# SCH_Bitcoin-Tracker_2024-07-20.net
KiCad netlist of a schematic drawn in EasyEDA
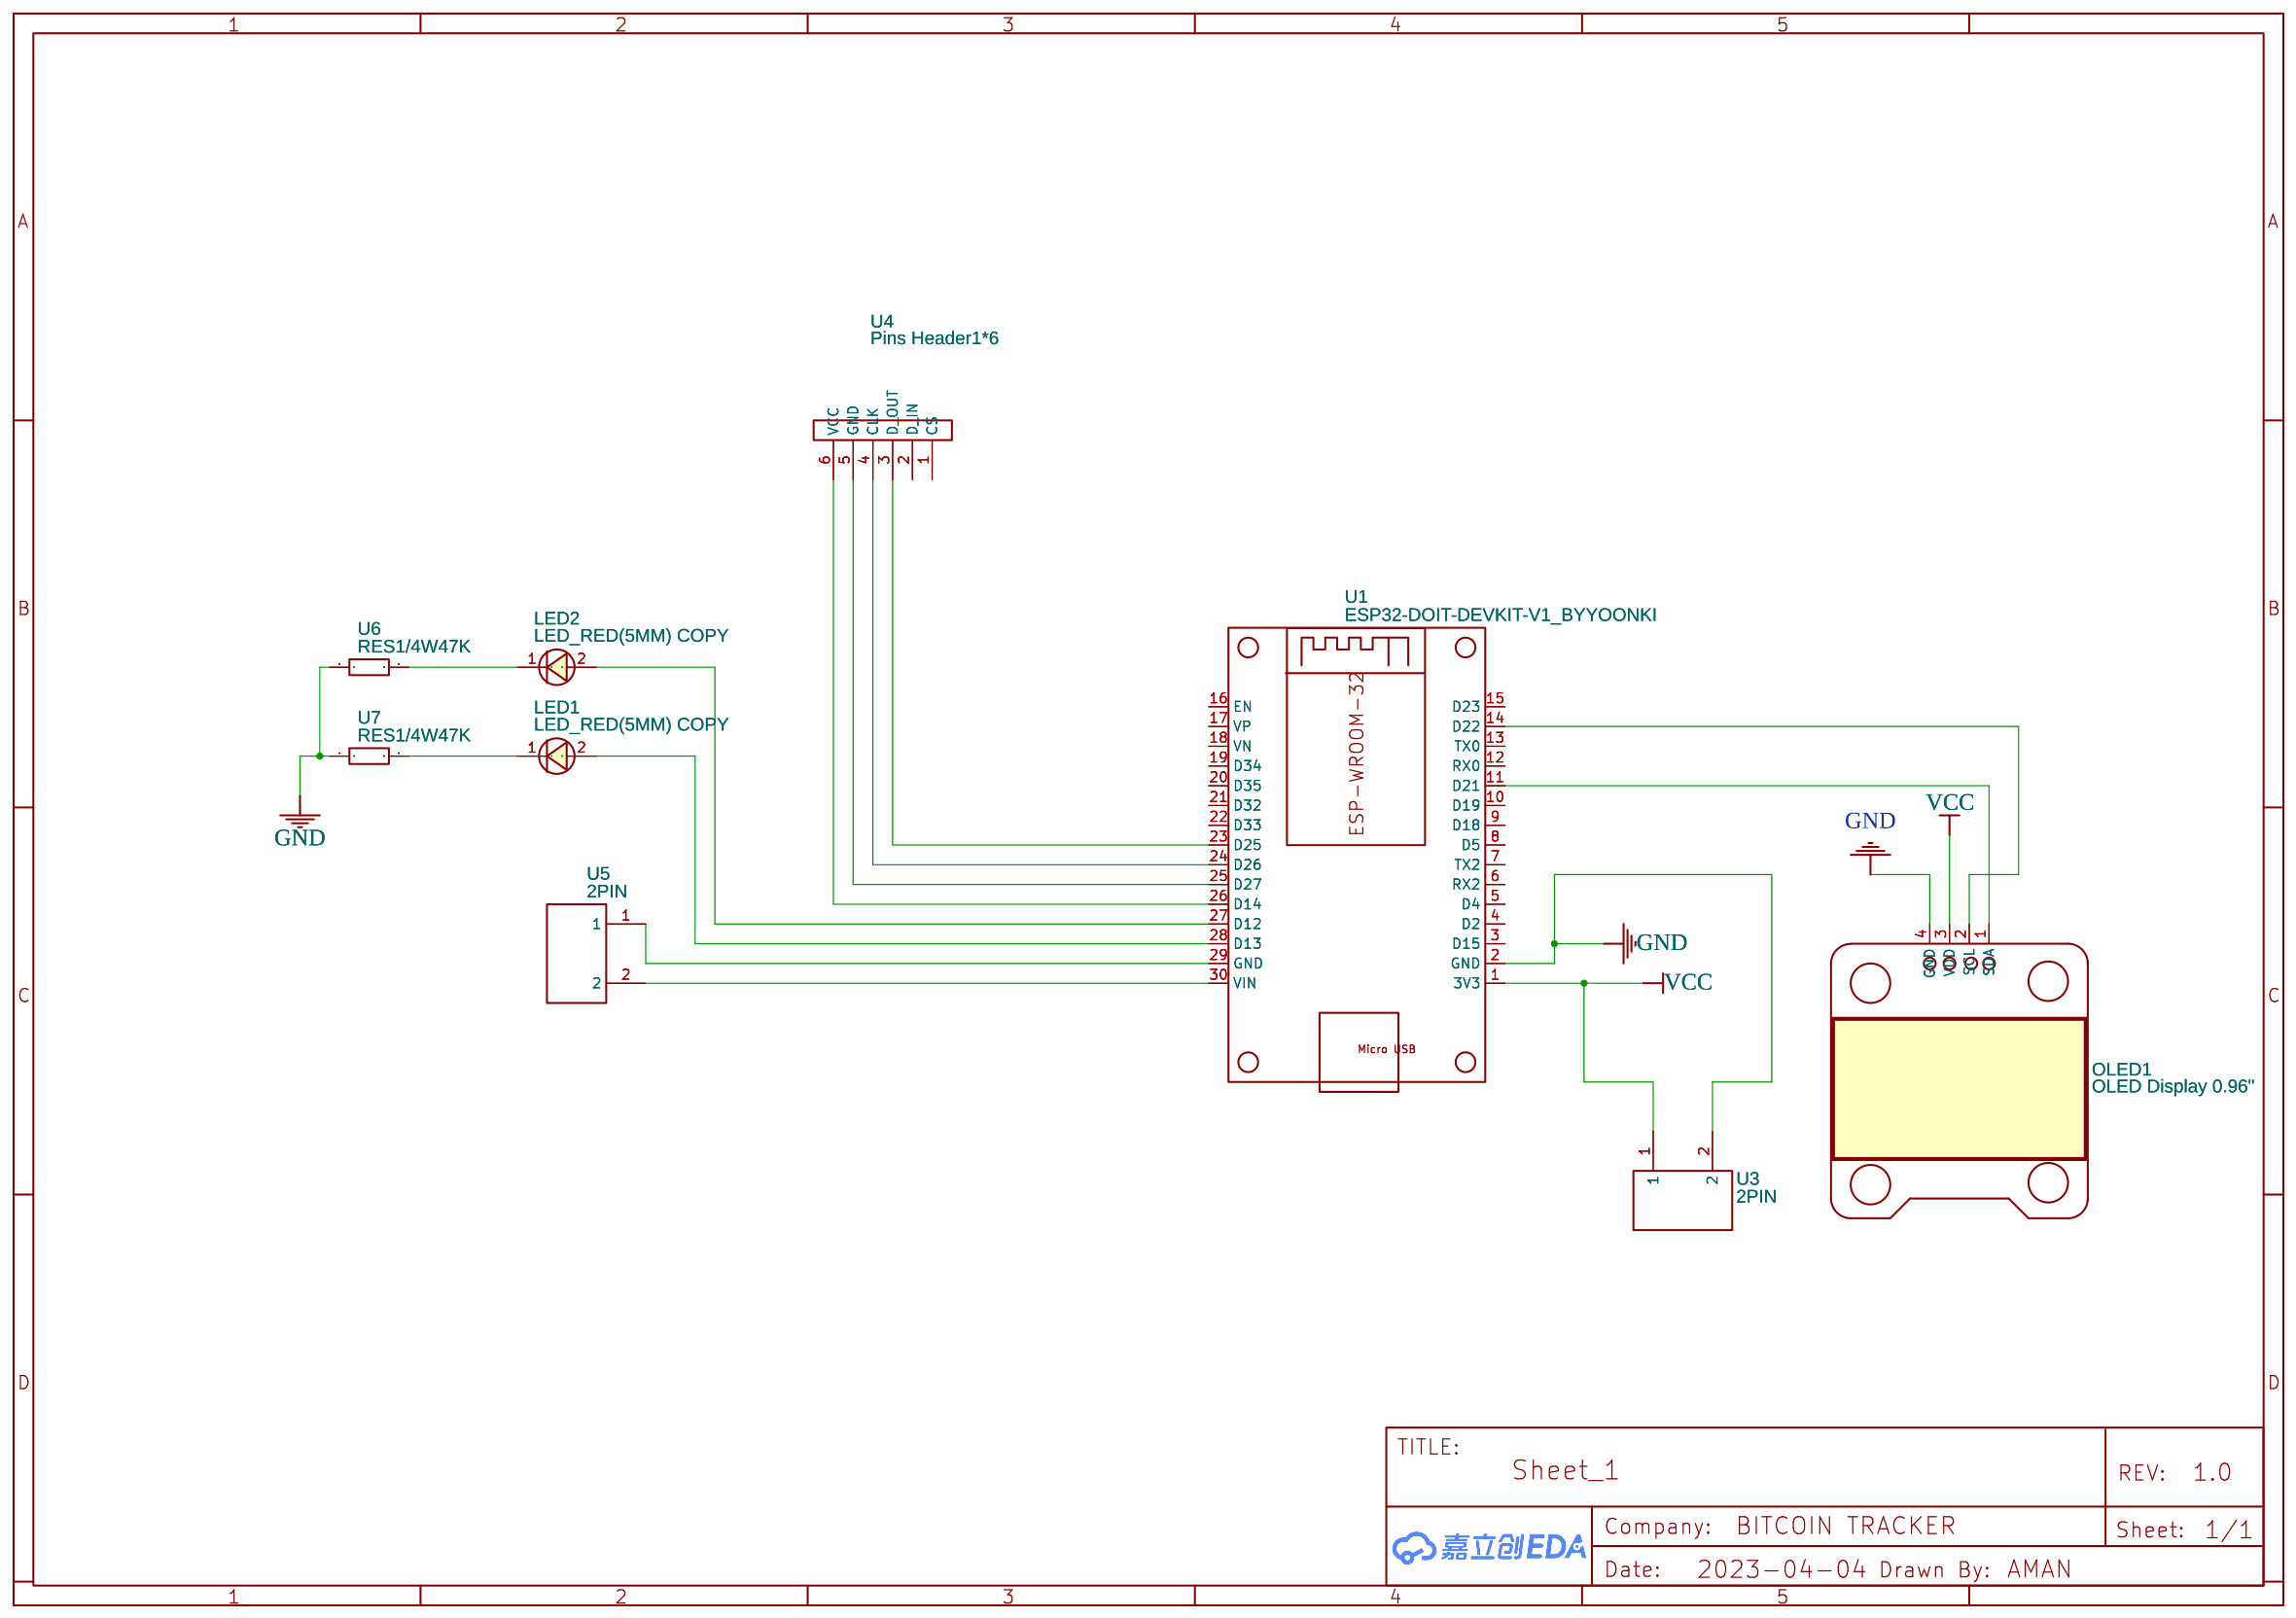
[diagram p0: schematic sheet]

(export (version "E")
  (design (tool "Eeschema 10.0.6"))
  (components
    (comp (ref "LED1")
      (value "LED_RED(5MM) COPY")
      (fields (field (name "Manufacturer Part") "LED 5MM"))
      (libsource (lib "") (part "LED_RED(5MM) COPY"))
    )
    (comp (ref "LED2")
      (value "LED_RED(5MM) COPY")
      (fields (field (name "Manufacturer Part") "LED 5MM"))
      (libsource (lib "") (part "LED_RED(5MM) COPY"))
    )
    (comp (ref "OLED1")
      (value "OLED Display 0.96\"")
      (libsource (lib "") (part "OLED Display 0.96{dblquote}"))
    )
    (comp (ref "U1")
      (value "ESP32-DOIT-DEVKIT-V1_BYYOONKI")
      (fields (field (name "Manufacturer Part") "ESP32_DOIT_DEVKIT_30_PIN"))
      (libsource (lib "") (part "ESP32-DOIT-DEVKIT-V1_BYYOONKI"))
    )
    (comp (ref "U3") (value "2PIN") (libsource (lib "") (part "2PIN_1")))
    (comp (ref "U4") (value "Pins Header1*6") (libsource (lib "") (part "Pins Header1*6")))
    (comp (ref "U5") (value "2PIN") (libsource (lib "") (part "2PIN")))
    (comp (ref "U6") (value "RES1/4W47K") (libsource (lib "") (part "RES1/4W47K")))
    (comp (ref "U7") (value "RES1/4W47K") (libsource (lib "") (part "RES1/4W47K")))
  )
  (nets
    (net (code "1") (name "GND") (class "Default")
      (node (ref "OLED1") (pin "4") (pinfunction "GND_4") (pintype "passive"))
      (node (ref "U1") (pin "2") (pinfunction "GND_2") (pintype "input"))
      (node (ref "U3") (pin "2") (pinfunction "2_2") (pintype "unspecified"))
      (node (ref "U6") (pin "1") (pinfunction "1_1") (pintype "input"))
      (node (ref "U7") (pin "1") (pinfunction "1_1") (pintype "input"))
    )
    (net (code "2") (name "Net-(LED1-A)") (class "Default")
      (node (ref "LED1") (pin "2") (pinfunction "A_2") (pintype "unspecified"))
      (node (ref "U1") (pin "28") (pinfunction "D13_28") (pintype "input"))
    )
    (net (code "3") (name "Net-(LED1-K)") (class "Default")
      (node (ref "LED1") (pin "1") (pinfunction "K_1") (pintype "unspecified"))
      (node (ref "U7") (pin "2") (pinfunction "2_2") (pintype "input"))
    )
    (net (code "4") (name "Net-(LED2-A)") (class "Default")
      (node (ref "LED2") (pin "2") (pinfunction "A_2") (pintype "unspecified"))
      (node (ref "U1") (pin "27") (pinfunction "D12_27") (pintype "input"))
    )
    (net (code "5") (name "Net-(LED2-K)") (class "Default")
      (node (ref "LED2") (pin "1") (pinfunction "K_1") (pintype "unspecified"))
      (node (ref "U6") (pin "2") (pinfunction "2_2") (pintype "input"))
    )
    (net (code "6") (name "Net-(OLED1-SCL)") (class "Default")
      (node (ref "OLED1") (pin "2") (pinfunction "SCL_2") (pintype "unspecified"))
      (node (ref "U1") (pin "14") (pinfunction "D22_14") (pintype "input"))
    )
    (net (code "7") (name "Net-(OLED1-SDA)") (class "Default")
      (node (ref "OLED1") (pin "1") (pinfunction "SDA_1") (pintype "unspecified"))
      (node (ref "U1") (pin "11") (pinfunction "D21_11") (pintype "input"))
    )
    (net (code "8") (name "Net-(U1-D14)") (class "Default")
      (node (ref "U1") (pin "26") (pinfunction "D14_26") (pintype "input"))
      (node (ref "U4") (pin "6") (pinfunction "VCC_6") (pintype "unspecified"))
    )
    (net (code "9") (name "Net-(U1-D25)") (class "Default")
      (node (ref "U1") (pin "23") (pinfunction "D25_23") (pintype "input"))
      (node (ref "U4") (pin "3") (pinfunction "D_OUT_3") (pintype "unspecified"))
    )
    (net (code "10") (name "Net-(U1-D26)") (class "Default")
      (node (ref "U1") (pin "24") (pinfunction "D26_24") (pintype "input"))
      (node (ref "U4") (pin "4") (pinfunction "CLK_4") (pintype "unspecified"))
    )
    (net (code "11") (name "Net-(U1-D27)") (class "Default")
      (node (ref "U1") (pin "25") (pinfunction "D27_25") (pintype "input"))
      (node (ref "U4") (pin "5") (pinfunction "GND_5") (pintype "unspecified"))
    )
    (net (code "12") (name "Net-(U1-GND-Pad29)") (class "Default")
      (node (ref "U1") (pin "29") (pinfunction "GND_29") (pintype "input"))
      (node (ref "U5") (pin "1") (pinfunction "1_1") (pintype "unspecified"))
    )
    (net (code "13") (name "Net-(U1-VIN)") (class "Default")
      (node (ref "U1") (pin "30") (pinfunction "VIN_30") (pintype "input"))
      (node (ref "U5") (pin "2") (pinfunction "2_2") (pintype "unspecified"))
    )
    (net (code "14") (name "VCC") (class "Default")
      (node (ref "OLED1") (pin "3") (pinfunction "VDD_3") (pintype "passive"))
      (node (ref "U1") (pin "1") (pinfunction "3V3_1") (pintype "input"))
      (node (ref "U3") (pin "1") (pinfunction "1_1") (pintype "unspecified"))
    )
    (net (code "15") (name "unconnected-(U1-D2-Pad4)") (class "Default")
      (node (ref "U1") (pin "4") (pinfunction "D2_4") (pintype "input"))
    )
    (net (code "16") (name "unconnected-(U1-D4-Pad5)") (class "Default")
      (node (ref "U1") (pin "5") (pinfunction "D4_5") (pintype "input"))
    )
    (net (code "17") (name "unconnected-(U1-D5-Pad8)") (class "Default")
      (node (ref "U1") (pin "8") (pinfunction "D5_8") (pintype "input"))
    )
    (net (code "18") (name "unconnected-(U1-D15-Pad3)") (class "Default")
      (node (ref "U1") (pin "3") (pinfunction "D15_3") (pintype "input"))
    )
    (net (code "19") (name "unconnected-(U1-D18-Pad9)") (class "Default")
      (node (ref "U1") (pin "9") (pinfunction "D18_9") (pintype "input"))
    )
    (net (code "20") (name "unconnected-(U1-D19-Pad10)") (class "Default")
      (node (ref "U1") (pin "10") (pinfunction "D19_10") (pintype "input"))
    )
    (net (code "21") (name "unconnected-(U1-D23-Pad15)") (class "Default")
      (node (ref "U1") (pin "15") (pinfunction "D23_15") (pintype "input"))
    )
    (net (code "22") (name "unconnected-(U1-D32-Pad21)") (class "Default")
      (node (ref "U1") (pin "21") (pinfunction "D32_21") (pintype "input"))
    )
    (net (code "23") (name "unconnected-(U1-D33-Pad22)") (class "Default")
      (node (ref "U1") (pin "22") (pinfunction "D33_22") (pintype "input"))
    )
    (net (code "24") (name "unconnected-(U1-D34-Pad19)") (class "Default")
      (node (ref "U1") (pin "19") (pinfunction "D34_19") (pintype "input"))
    )
    (net (code "25") (name "unconnected-(U1-D35-Pad20)") (class "Default")
      (node (ref "U1") (pin "20") (pinfunction "D35_20") (pintype "input"))
    )
    (net (code "26") (name "unconnected-(U1-EN-Pad16)") (class "Default")
      (node (ref "U1") (pin "16") (pinfunction "EN_16") (pintype "input"))
    )
    (net (code "27") (name "unconnected-(U1-RX0-Pad12)") (class "Default")
      (node (ref "U1") (pin "12") (pinfunction "RX0_12") (pintype "input"))
    )
    (net (code "28") (name "unconnected-(U1-RX2-Pad6)") (class "Default")
      (node (ref "U1") (pin "6") (pinfunction "RX2_6") (pintype "input"))
    )
    (net (code "29") (name "unconnected-(U1-TX0-Pad13)") (class "Default")
      (node (ref "U1") (pin "13") (pinfunction "TX0_13") (pintype "input"))
    )
    (net (code "30") (name "unconnected-(U1-TX2-Pad7)") (class "Default")
      (node (ref "U1") (pin "7") (pinfunction "TX2_7") (pintype "input"))
    )
    (net (code "31") (name "unconnected-(U1-VN-Pad18)") (class "Default")
      (node (ref "U1") (pin "18") (pinfunction "VN_18") (pintype "input"))
    )
    (net (code "32") (name "unconnected-(U1-VP-Pad17)") (class "Default")
      (node (ref "U1") (pin "17") (pinfunction "VP_17") (pintype "input"))
    )
    (net (code "33") (name "unconnected-(U4-CS-Pad1)") (class "Default")
      (node (ref "U4") (pin "1") (pinfunction "CS_1") (pintype "unspecified"))
    )
    (net (code "34") (name "unconnected-(U4-D_IN-Pad2)") (class "Default")
      (node (ref "U4") (pin "2") (pinfunction "D_IN_2") (pintype "unspecified"))
    )
  )
)
